# DataTranslator.net
KiCad netlist of a schematic drawn in Altium Designer
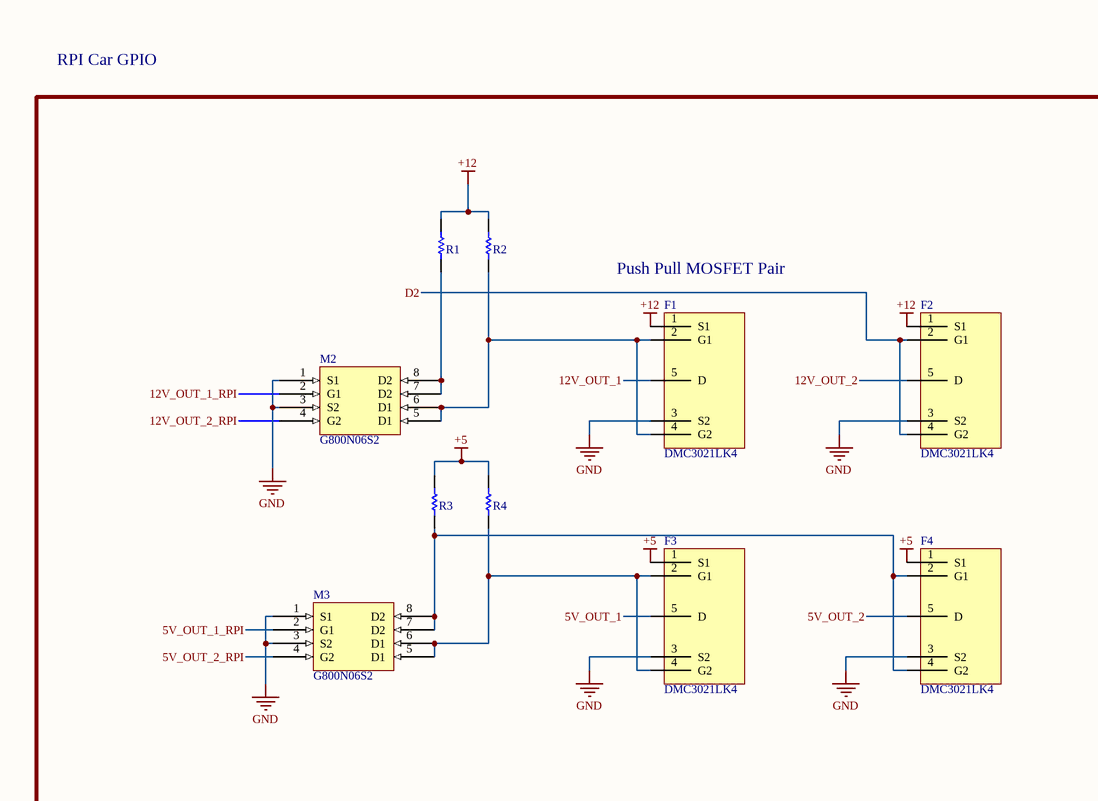
[diagram p0: DataTranslator.SchDoc, left]
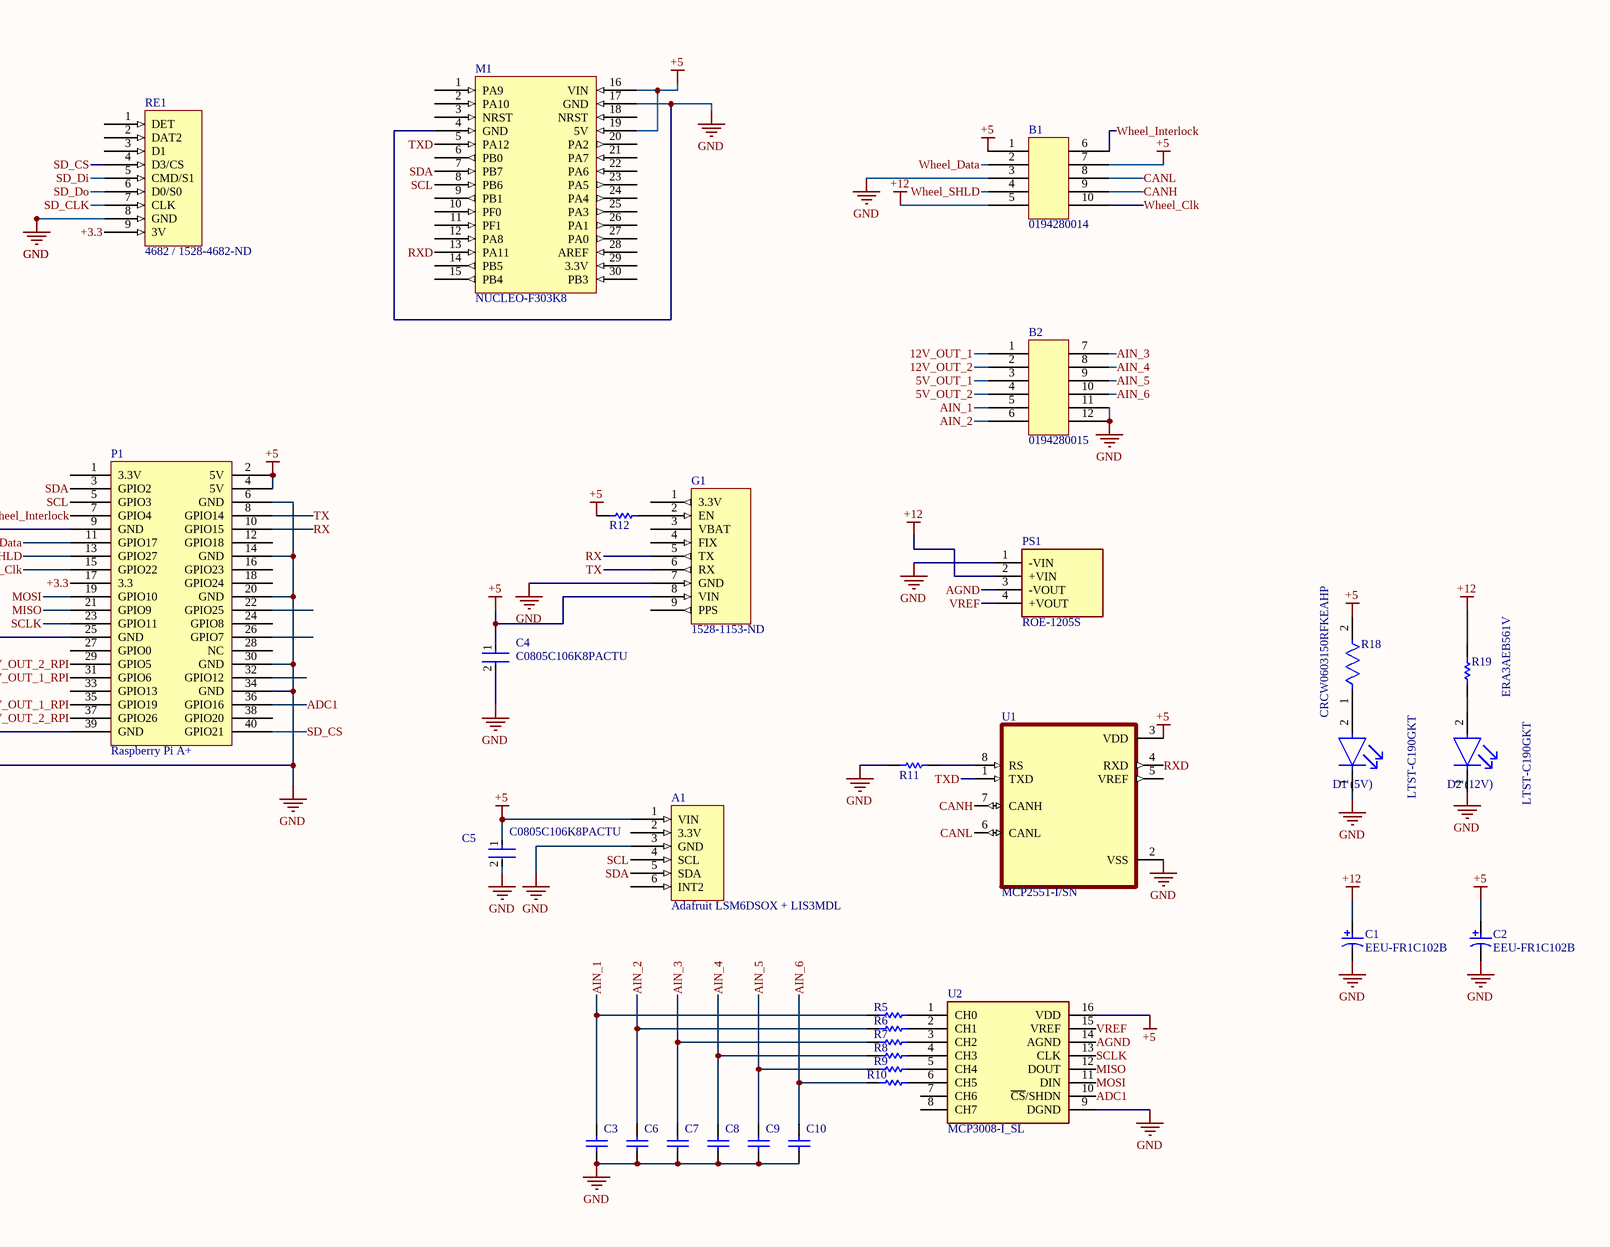
[diagram p1: DataTranslator.SchDoc, right]

(export (version "E")
  (design (tool "Eeschema 10.0.6"))
  (components
    (comp (ref "A1")
      (value "Adafruit LSM6DSOX + LIS3MDL")
      (footprint "4097 Accelerometer")
      (description "ADXL343 - TRIPLE-AXIS ACCELEROMETER")
      (fields
        (field (name "MANUFACTURER") "Adafruit Industries")
        (field (name "MANUFACTURER PART NUMBER") "4097")
      )
      (libsource (lib "DataTranslator") (part "4097"))
    )
    (comp (ref "B1")
      (value "0194280014")
      (footprint "0194280014")
      (description "Combination Line Connector, 10 Contact(s), Male, Solder Terminal")
      (fields (field (name "MANUFACTURER") "Molex"))
      (libsource (lib "DataTranslator") (part "0194280014"))
    )
    (comp (ref "B2")
      (value "0194280015")
      (footprint "0194280015")
      (description "Combination Line Connector")
      (fields (field (name "MANUFACTURER") "Molex") (field (name "MANUFACTURER PART NUMBER") "0194280014"))
      (libsource (lib "DataTranslator") (part "0194280015"))
    )
    (comp (ref "C1")
      (value "EEU-FR1C102B")
      (footprint "PNSC-EEUFM1H221-2")
      (fields (field (name "MANUFACTURER") "Panasonic"))
      (libsource (lib "Altium Content Vault") (part "CAP-P-2"))
    )
    (comp (ref "C2")
      (value "EEU-FR1C102B")
      (footprint "PNSC-EEUFM1H221-2")
      (fields (field (name "MANUFACTURER") "Panasonic"))
      (libsource (lib "Altium Content Vault") (part "CAP-P-2"))
    )
    (comp (ref "C3")
      (value "C0805C105K4PACTU")
      (footprint "CAPC2013X145X50LL20T25")
      (fields (field (name "MANUFACTURER") "Kemet"))
      (libsource (lib "Altium Content Vault") (part "CAP"))
    )
    (comp (ref "C4")
      (value "C0805C106K8PACTU")
      (footprint "FP-C0805C-DG-MFG")
      (description "CAP CER 10UF 10V X5R 0805")
      (fields (field (name "TOLERANCE") "10%") (field (name "MANUFACTURER") "Kemet"))
      (libsource (lib "Altium Content Vault") (part "11868f565c42a9108669ba33697ecf6"))
    )
    (comp (ref "C5")
      (value "C0805C106K8PACTU")
      (footprint "FP-C0805C-DG-MFG")
      (description "CAP CER 10UF 10V X5R 0805")
      (fields (field (name "TOLERANCE") "10%") (field (name "MANUFACTURER") "Kemet"))
      (libsource (lib "Altium Content Vault") (part "11868f565c42a9108669ba33697ecf6"))
    )
    (comp (ref "C6")
      (value "C0805C105K4PACTU")
      (footprint "CAPC2013X145X50LL20T25")
      (fields (field (name "MANUFACTURER") "Kemet"))
      (libsource (lib "Altium Content Vault") (part "CAP"))
    )
    (comp (ref "C7")
      (value "C0805C105K4PACTU")
      (footprint "CAPC2013X145X50LL20T25")
      (fields (field (name "MANUFACTURER") "Kemet"))
      (libsource (lib "Altium Content Vault") (part "CAP"))
    )
    (comp (ref "C8")
      (value "C0805C105K4PACTU")
      (footprint "CAPC2013X145X50LL20T25")
      (fields (field (name "MANUFACTURER") "Kemet"))
      (libsource (lib "Altium Content Vault") (part "CAP"))
    )
    (comp (ref "C9")
      (value "C0805C105K4PACTU")
      (footprint "CAPC2013X145X50LL20T25")
      (fields (field (name "MANUFACTURER") "Kemet"))
      (libsource (lib "Altium Content Vault") (part "CAP"))
    )
    (comp (ref "C10")
      (value "C0805C105K4PACTU")
      (footprint "CAPC2013X145X50LL20T25")
      (fields (field (name "MANUFACTURER") "Kemet"))
      (libsource (lib "Altium Content Vault") (part "CAP"))
    )
    (comp (ref "D1 (5V)")
      (value "LTST-C190GKT")
      (footprint "FP-LTST-C190GKT-MFG")
      (description "LED GREEN CLEAR CHIP SMD")
      (fields (field (name "VOLTAGE") "2V"))
      (libsource (lib "Altium Content Vault") (part "8706943c75ba83719d021d2fdc84c58"))
    )
    (comp (ref "D2 (12V)")
      (value "LTST-C190GKT")
      (footprint "FP-LTST-C190GKT-MFG")
      (description "LED GREEN CLEAR CHIP SMD")
      (fields (field (name "VOLTAGE") "2V"))
      (libsource (lib "Altium Content Vault") (part "8706943c75ba83719d021d2fdc84c58"))
    )
    (comp (ref "F1")
      (value "DMC3021LK4")
      (footprint "DMC3021LK4")
      (fields
        (field (name "MANUFACTURER") "Diodes")
        (field (name "MANUFACTURER PART NUMBER") "DMC3021LK4-13")
      )
      (libsource (lib "DataTranslator") (part "DMC3021LK4"))
    )
    (comp (ref "F2")
      (value "DMC3021LK4")
      (footprint "DMC3021LK4")
      (fields
        (field (name "MANUFACTURER") "Diodes")
        (field (name "MANUFACTURER PART NUMBER") "DMC3021LK4-13")
      )
      (libsource (lib "DataTranslator") (part "DMC3021LK4"))
    )
    (comp (ref "F3")
      (value "DMC3021LK4")
      (footprint "DMC3021LK4")
      (fields
        (field (name "MANUFACTURER") "Diodes")
        (field (name "MANUFACTURER PART NUMBER") "DMC3021LK4-13")
      )
      (libsource (lib "DataTranslator") (part "DMC3021LK4"))
    )
    (comp (ref "F4")
      (value "DMC3021LK4")
      (footprint "DMC3021LK4")
      (fields
        (field (name "MANUFACTURER") "Diodes")
        (field (name "MANUFACTURER PART NUMBER") "DMC3021LK4-13")
      )
      (libsource (lib "DataTranslator") (part "DMC3021LK4"))
    )
    (comp (ref "G1")
      (value "1528-1153-ND")
      (footprint "GPS")
      (description "GPS BREAKOUT 66CH W/10HZ UPDATES")
      (fields
        (field (name "MANUFACTURER") "Adafruit Industries")
        (field (name "MANUFACTURER PART NUMBER") "746")
      )
      (libsource (lib "DataTranslator") (part "1528-1153-ND"))
    )
    (comp (ref "M1")
      (value "NUCLEO-F303K8")
      (footprint "STM Footprint")
      (description "Boards/Accessories")
      (fields (field (name "MANUFACTURER") "STMicroelectronics"))
      (libsource (lib "DataTranslator") (part "NUCLEO-F303K8"))
    )
    (comp (ref "M2")
      (value "G800N06S2")
      (footprint "G800N06S2")
      (description "DUAL N-Channel Enhancement Mode Power MOSFET")
      (fields (field (name "MANUFACTURER") "GoFord"))
      (libsource (lib "DataTranslator") (part "G800N06S2"))
    )
    (comp (ref "M3")
      (value "G800N06S2")
      (footprint "G800N06S2")
      (description "DUAL N-Channel Enhancement Mode Power MOSFET")
      (fields (field (name "MANUFACTURER") "GoFord"))
      (libsource (lib "DataTranslator") (part "G800N06S2"))
    )
    (comp (ref "P1")
      (value "Raspberry Pi A+")
      (footprint "Raspberry Pi A+")
      (description "SINGLE BOARD COMPUTER 700MHZ 256")
      (fields
        (field (name "MANUFACTURER") "Raspberry Pi")
        (field (name "MANUFACTURER PART NUMBER") "RASPBERRY PI A+")
      )
      (libsource (lib "DataTranslator") (part "Raspberry Pi A+"))
    )
    (comp (ref "PS1")
      (value "ROE-1205S")
      (footprint "ROE-1205S")
      (description "Recom Through Hole 1W Isolated DC-DC Converter, I/O isolation 1kV dc, Vout 5V dc")
      (fields (field (name "MOUSER PART NUMBER") "919-ROE-1205S"))
      (libsource (lib "DataTranslator") (part "ROE-1205S"))
    )
    (comp (ref "R1")
      (value "RC0805FR-0710KL")
      (footprint "RESC2013X60X35NL10T20")
      (description "Chip Resistor, 10 KOhm, +/- 1%, 0.125 W, -55 to 155 degC, 0805 (2012 Metric), RoHS, Tape and Reel")
      (fields (field (name "MANUFACTURER") "Yageo"))
      (libsource (lib "Altium Content Vault") (part "RES-2"))
    )
    (comp (ref "R2")
      (value "RC0805FR-0710KL")
      (footprint "RESC2013X60X35NL10T20")
      (description "Chip Resistor, 10 KOhm, +/- 1%, 0.125 W, -55 to 155 degC, 0805 (2012 Metric), RoHS, Tape and Reel")
      (fields (field (name "MANUFACTURER") "Yageo"))
      (libsource (lib "Altium Content Vault") (part "RES-2"))
    )
    (comp (ref "R3")
      (value "RC0805FR-0710KL")
      (footprint "RESC2013X60X35NL10T20")
      (description "Chip Resistor, 10 KOhm, +/- 1%, 0.125 W, -55 to 155 degC, 0805 (2012 Metric), RoHS, Tape and Reel")
      (fields (field (name "MANUFACTURER") "Yageo"))
      (libsource (lib "Altium Content Vault") (part "RES-2"))
    )
    (comp (ref "R4")
      (value "RC0805FR-0710KL")
      (footprint "RESC2013X60X35NL10T20")
      (description "Chip Resistor, 10 KOhm, +/- 1%, 0.125 W, -55 to 155 degC, 0805 (2012 Metric), RoHS, Tape and Reel")
      (fields (field (name "MANUFACTURER") "Yageo"))
      (libsource (lib "Altium Content Vault") (part "RES-2"))
    )
    (comp (ref "R5")
      (value "RC0805FR-0710KL")
      (footprint "RESC2013X60X35NL10T20")
      (description "Chip Resistor, 10 KOhm, +/- 1%, 0.125 W, -55 to 155 degC, 0805 (2012 Metric), RoHS, Tape and Reel")
      (fields (field (name "MANUFACTURER") "Yageo"))
      (libsource (lib "Altium Content Vault") (part "RES-2"))
    )
    (comp (ref "R6")
      (value "RC0805FR-0710KL")
      (footprint "RESC2013X60X35NL10T20")
      (description "Chip Resistor, 10 KOhm, +/- 1%, 0.125 W, -55 to 155 degC, 0805 (2012 Metric), RoHS, Tape and Reel")
      (fields (field (name "MANUFACTURER") "Yageo"))
      (libsource (lib "Altium Content Vault") (part "RES-2"))
    )
    (comp (ref "R7")
      (value "RC0805FR-0710KL")
      (footprint "RESC2013X60X35NL10T20")
      (description "Chip Resistor, 10 KOhm, +/- 1%, 0.125 W, -55 to 155 degC, 0805 (2012 Metric), RoHS, Tape and Reel")
      (fields (field (name "MANUFACTURER") "Yageo"))
      (libsource (lib "Altium Content Vault") (part "RES-2"))
    )
    (comp (ref "R8")
      (value "RC0805FR-0710KL")
      (footprint "RESC2013X60X35NL10T20")
      (description "Chip Resistor, 10 KOhm, +/- 1%, 0.125 W, -55 to 155 degC, 0805 (2012 Metric), RoHS, Tape and Reel")
      (fields (field (name "MANUFACTURER") "Yageo"))
      (libsource (lib "Altium Content Vault") (part "RES-2"))
    )
    (comp (ref "R9")
      (value "RC0805FR-0710KL")
      (footprint "RESC2013X60X35NL10T20")
      (description "Chip Resistor, 10 KOhm, +/- 1%, 0.125 W, -55 to 155 degC, 0805 (2012 Metric), RoHS, Tape and Reel")
      (fields (field (name "MANUFACTURER") "Yageo"))
      (libsource (lib "Altium Content Vault") (part "RES-2"))
    )
    (comp (ref "R10")
      (value "RC0805FR-0710KL")
      (footprint "RESC2013X60X35NL10T20")
      (description "Chip Resistor, 10 KOhm, +/- 1%, 0.125 W, -55 to 155 degC, 0805 (2012 Metric), RoHS, Tape and Reel")
      (fields (field (name "MANUFACTURER") "Yageo"))
      (libsource (lib "Altium Content Vault") (part "RES-2"))
    )
    (comp (ref "R11")
      (value "RC0805FR-0710KL")
      (footprint "RESC2013X60X35NL10T20")
      (description "Chip Resistor, 10 KOhm, +/- 1%, 0.125 W, -55 to 155 degC, 0805 (2012 Metric), RoHS, Tape and Reel")
      (fields (field (name "MANUFACTURER") "Yageo"))
      (libsource (lib "Altium Content Vault") (part "RES-2"))
    )
    (comp (ref "R12")
      (value "RC0805FR-0710KL")
      (footprint "RESC2013X60X35NL10T20")
      (description "Chip Resistor, 10 KOhm, +/- 1%, 0.125 W, -55 to 155 degC, 0805 (2012 Metric), RoHS, Tape and Reel")
      (fields (field (name "MANUFACTURER") "Yageo"))
      (libsource (lib "Altium Content Vault") (part "RES-2"))
    )
    (comp (ref "R18")
      (value "CRCW0603150RFKEAHP")
      (footprint "FP-CRCW0603-HPe3-MFG")
      (description "RES Thick Film, 150Ω, 1%, 0.33W, 100ppm/°C, 0603")
      (fields (field (name "TOLERANCE") "1%"))
      (libsource (lib "Altium Content Vault") (part "1029c3af85768c4190bb7ad29bc67b5"))
    )
    (comp (ref "R19")
      (value "ERA3AEB561V")
      (footprint "RESC1608X55X30LL20T20")
      (fields (field (name "MANUFACTURER") "Panasonic"))
      (libsource (lib "Altium Content Vault") (part "RES"))
    )
    (comp (ref "RE1")
      (value "4682 / 1528-4682-ND")
      (footprint "SDCARD")
      (description "MICROSD SPI/SPIO BREAKOUT BOARD")
      (fields
        (field (name "MANUFACTURER") "Adafruit Industries")
        (field (name "MANUFACTURER PART NUMBER") "4682")
      )
      (libsource (lib "DataTranslator") (part "4682"))
    )
    (comp (ref "U1")
      (value "MCP2551-I/SN")
      (footprint "CAN Transceiver")
      (description "CAN Transceiver, 1-Trnsvr, PDSO8")
      (fields (field (name "MANUFACTURER") "Microchip"))
      (libsource (lib "DataTranslator") (part "MCP2551-I/SN"))
    )
    (comp (ref "U2")
      (value "MCP3008-I_SL")
      (footprint "SOIC127P600X175-16N")
      (fields
        (field (name "MANUFACTURER_PART_NUMBER") "MCP3008-I/SL")
        (field (name "MOUSER PART NUMBER") "579-MCP3008-I/SL")
      )
      (libsource (lib "DataTranslator") (part "MCP3008-I_SL"))
    )
  )
  (nets
    (net (code "1") (name "+5") (class "Default")
      (node (ref "A1") (pin "1") (pinfunction "VIN_1") (pintype "input"))
      (node (ref "B1") (pin "1") (pintype "passive"))
      (node (ref "B1") (pin "7") (pintype "passive"))
      (node (ref "C2") (pin "1") (pinfunction "1_1") (pintype "passive"))
      (node (ref "C4") (pin "1") (pinfunction "1_1") (pintype "passive"))
      (node (ref "C5") (pin "1") (pinfunction "1_1") (pintype "passive"))
      (node (ref "F3") (pin "1") (pinfunction "S1_1") (pintype "passive"))
      (node (ref "F4") (pin "1") (pinfunction "S1_1") (pintype "passive"))
      (node (ref "G1") (pin "8") (pinfunction "VIN_8") (pintype "input"))
      (node (ref "M1") (pin "16") (pinfunction "VIN_16") (pintype "input"))
      (node (ref "M1") (pin "19") (pinfunction "5V_19") (pintype "input"))
      (node (ref "P1") (pin "2") (pinfunction "5V_2") (pintype "passive"))
      (node (ref "P1") (pin "4") (pinfunction "5V_4") (pintype "passive"))
      (node (ref "R12") (pin "1") (pinfunction "1_1") (pintype "passive"))
      (node (ref "R18") (pin "2") (pinfunction "2_2") (pintype "passive"))
      (node (ref "R3") (pin "2") (pinfunction "2_2") (pintype "passive"))
      (node (ref "R4") (pin "2") (pinfunction "2_2") (pintype "passive"))
      (node (ref "U1") (pin "3") (pinfunction "VDD_3") (pintype "power_in"))
      (node (ref "U2") (pin "16") (pinfunction "VDD_16") (pintype "passive"))
    )
    (net (code "2") (name "+12") (class "Default")
      (node (ref "B1") (pin "5") (pintype "passive"))
      (node (ref "C1") (pin "1") (pinfunction "1_1") (pintype "passive"))
      (node (ref "F1") (pin "1") (pinfunction "S1_1") (pintype "passive"))
      (node (ref "F2") (pin "1") (pinfunction "S1_1") (pintype "passive"))
      (node (ref "PS1") (pin "2") (pinfunction "+VIN_2") (pintype "passive"))
      (node (ref "R1") (pin "2") (pinfunction "2_2") (pintype "passive"))
      (node (ref "R19") (pin "2") (pinfunction "2_2") (pintype "passive"))
      (node (ref "R2") (pin "2") (pinfunction "2_2") (pintype "passive"))
    )
    (net (code "3") (name "/+3.3") (class "Default")
      (node (ref "P1") (pin "17") (pinfunction "3.3_17") (pintype "passive"))
      (node (ref "RE1") (pin "9") (pinfunction "3V_9") (pintype "input"))
    )
    (net (code "4") (name "/5V_OUT_1") (class "Default")
      (node (ref "B2") (pin "3") (pintype "passive"))
      (node (ref "F3") (pin "5") (pinfunction "D_5") (pintype "passive"))
    )
    (net (code "5") (name "/5V_OUT_1_RPI") (class "Default")
      (node (ref "M3") (pin "2") (pinfunction "G1_2") (pintype "input"))
      (node (ref "P1") (pin "35") (pinfunction "GPIO19_35") (pintype "passive"))
    )
    (net (code "6") (name "/5V_OUT_2") (class "Default")
      (node (ref "B2") (pin "4") (pintype "passive"))
      (node (ref "F4") (pin "5") (pinfunction "D_5") (pintype "passive"))
    )
    (net (code "7") (name "/5V_OUT_2_RPI") (class "Default")
      (node (ref "M3") (pin "4") (pinfunction "G2_4") (pintype "input"))
      (node (ref "P1") (pin "37") (pinfunction "GPIO26_37") (pintype "passive"))
    )
    (net (code "8") (name "/12V_OUT_1") (class "Default")
      (node (ref "B2") (pin "1") (pintype "passive"))
      (node (ref "F1") (pin "5") (pinfunction "D_5") (pintype "passive"))
    )
    (net (code "9") (name "/12V_OUT_1_RPI") (class "Default")
      (node (ref "M2") (pin "2") (pinfunction "G1_2") (pintype "input"))
      (node (ref "P1") (pin "31") (pinfunction "GPIO6_31") (pintype "passive"))
    )
    (net (code "10") (name "/12V_OUT_2") (class "Default")
      (node (ref "B2") (pin "2") (pintype "passive"))
      (node (ref "F2") (pin "5") (pinfunction "D_5") (pintype "passive"))
    )
    (net (code "11") (name "/12V_OUT_2_RPI") (class "Default")
      (node (ref "M2") (pin "4") (pinfunction "G2_4") (pintype "input"))
      (node (ref "P1") (pin "29") (pinfunction "GPIO5_29") (pintype "passive"))
    )
    (net (code "12") (name "/ADC1") (class "Default")
      (node (ref "P1") (pin "36") (pinfunction "GPIO16_36") (pintype "passive"))
      (node (ref "U2") (pin "10") (pinfunction "~{CS}/SHDN_10") (pintype "passive"))
    )
    (net (code "13") (name "/AGND") (class "Default")
      (node (ref "PS1") (pin "3") (pinfunction "-VOUT_3") (pintype "passive"))
      (node (ref "U2") (pin "14") (pinfunction "AGND_14") (pintype "passive"))
    )
    (net (code "14") (name "/AIN_1") (class "Default")
      (node (ref "B2") (pin "5") (pintype "passive"))
      (node (ref "C3") (pin "1") (pinfunction "1_1") (pintype "passive"))
      (node (ref "R5") (pin "1") (pinfunction "1_1") (pintype "passive"))
    )
    (net (code "15") (name "/AIN_2") (class "Default")
      (node (ref "B2") (pin "6") (pintype "passive"))
      (node (ref "C6") (pin "1") (pinfunction "1_1") (pintype "passive"))
      (node (ref "R6") (pin "1") (pinfunction "1_1") (pintype "passive"))
    )
    (net (code "16") (name "/AIN_3") (class "Default")
      (node (ref "B2") (pin "7") (pintype "passive"))
      (node (ref "C7") (pin "1") (pinfunction "1_1") (pintype "passive"))
      (node (ref "R7") (pin "1") (pinfunction "1_1") (pintype "passive"))
    )
    (net (code "17") (name "/AIN_4") (class "Default")
      (node (ref "B2") (pin "8") (pintype "passive"))
      (node (ref "C8") (pin "1") (pinfunction "1_1") (pintype "passive"))
      (node (ref "R8") (pin "1") (pinfunction "1_1") (pintype "passive"))
    )
    (net (code "18") (name "/AIN_5") (class "Default")
      (node (ref "B2") (pin "9") (pintype "passive"))
      (node (ref "C9") (pin "1") (pinfunction "1_1") (pintype "passive"))
      (node (ref "R9") (pin "1") (pinfunction "1_1") (pintype "passive"))
    )
    (net (code "19") (name "/AIN_6") (class "Default")
      (node (ref "B2") (pin "10") (pintype "passive"))
      (node (ref "C10") (pin "1") (pinfunction "1_1") (pintype "passive"))
      (node (ref "R10") (pin "1") (pinfunction "1_1") (pintype "passive"))
    )
    (net (code "20") (name "/CANH") (class "Default")
      (node (ref "B1") (pin "9") (pintype "passive"))
      (node (ref "U1") (pin "7") (pinfunction "CANH_7") (pintype "bidirectional"))
    )
    (net (code "21") (name "/CANL") (class "Default")
      (node (ref "B1") (pin "8") (pintype "passive"))
      (node (ref "U1") (pin "6") (pinfunction "CANL_6") (pintype "bidirectional"))
    )
    (net (code "22") (name "/D2") (class "Default")
      (node (ref "F2") (pin "2") (pinfunction "G1_2") (pintype "passive"))
      (node (ref "F2") (pin "4") (pinfunction "G2_4") (pintype "passive"))
    )
    (net (code "23") (name "/MISO") (class "Default")
      (node (ref "P1") (pin "21") (pinfunction "GPIO9_21") (pintype "passive"))
      (node (ref "U2") (pin "12") (pinfunction "DOUT_12") (pintype "passive"))
    )
    (net (code "24") (name "/MOSI") (class "Default")
      (node (ref "P1") (pin "19") (pinfunction "GPIO10_19") (pintype "passive"))
      (node (ref "U2") (pin "11") (pinfunction "DIN_11") (pintype "passive"))
    )
    (net (code "25") (name "/RX") (class "Default")
      (node (ref "G1") (pin "5") (pinfunction "TX_5") (pintype "output"))
      (node (ref "P1") (pin "10") (pinfunction "GPIO15_10") (pintype "passive"))
    )
    (net (code "26") (name "/RXD") (class "Default")
      (node (ref "M1") (pin "13") (pinfunction "PA11_13") (pintype "input"))
      (node (ref "U1") (pin "4") (pinfunction "RXD_4") (pintype "output"))
    )
    (net (code "27") (name "/SCL") (class "Default")
      (node (ref "A1") (pin "4") (pinfunction "SCL_4") (pintype "input"))
      (node (ref "M1") (pin "8") (pinfunction "PB6_8") (pintype "input"))
      (node (ref "P1") (pin "5") (pinfunction "GPIO3_5") (pintype "passive"))
    )
    (net (code "28") (name "/SCLK") (class "Default")
      (node (ref "P1") (pin "23") (pinfunction "GPIO11_23") (pintype "passive"))
      (node (ref "U2") (pin "13") (pinfunction "CLK_13") (pintype "passive"))
    )
    (net (code "29") (name "/SDA") (class "Default")
      (node (ref "A1") (pin "5") (pinfunction "SDA_5") (pintype "input"))
      (node (ref "M1") (pin "7") (pinfunction "PB7_7") (pintype "input"))
      (node (ref "P1") (pin "3") (pinfunction "GPIO2_3") (pintype "passive"))
    )
    (net (code "30") (name "/SD_CLK") (class "Default")
      (node (ref "RE1") (pin "7") (pinfunction "CLK_7") (pintype "input"))
    )
    (net (code "31") (name "/SD_CS") (class "Default")
      (node (ref "P1") (pin "40") (pinfunction "GPIO21_40") (pintype "passive"))
      (node (ref "RE1") (pin "4") (pinfunction "D3/CS_4") (pintype "input"))
    )
    (net (code "32") (name "/SD_Di") (class "Default")
      (node (ref "RE1") (pin "5") (pinfunction "CMD/S1_5") (pintype "input"))
    )
    (net (code "33") (name "/SD_Do") (class "Default")
      (node (ref "RE1") (pin "6") (pinfunction "D0/S0_6") (pintype "input"))
    )
    (net (code "34") (name "/TX") (class "Default")
      (node (ref "G1") (pin "6") (pinfunction "RX_6") (pintype "output"))
      (node (ref "P1") (pin "8") (pinfunction "GPIO14_8") (pintype "passive"))
    )
    (net (code "35") (name "/TXD") (class "Default")
      (node (ref "M1") (pin "5") (pinfunction "PA12_5") (pintype "input"))
      (node (ref "U1") (pin "1") (pinfunction "TXD_1") (pintype "input"))
    )
    (net (code "36") (name "/VREF") (class "Default")
      (node (ref "PS1") (pin "4") (pinfunction "+VOUT_4") (pintype "passive"))
      (node (ref "U2") (pin "15") (pinfunction "VREF_15") (pintype "passive"))
    )
    (net (code "37") (name "/Wheel_Clk") (class "Default")
      (node (ref "B1") (pin "10") (pintype "passive"))
      (node (ref "P1") (pin "15") (pinfunction "GPIO22_15") (pintype "passive"))
    )
    (net (code "38") (name "/Wheel_Data") (class "Default")
      (node (ref "B1") (pin "2") (pintype "passive"))
      (node (ref "P1") (pin "11") (pinfunction "GPIO17_11") (pintype "passive"))
    )
    (net (code "39") (name "/Wheel_Interlock") (class "Default")
      (node (ref "B1") (pin "6") (pintype "passive"))
      (node (ref "P1") (pin "7") (pinfunction "GPIO4_7") (pintype "passive"))
    )
    (net (code "40") (name "/Wheel_SHLD") (class "Default")
      (node (ref "B1") (pin "4") (pintype "passive"))
      (node (ref "P1") (pin "13") (pinfunction "GPIO27_13") (pintype "passive"))
    )
    (net (code "41") (name "GND") (class "Default")
      (node (ref "A1") (pin "3") (pinfunction "GND_3") (pintype "input"))
      (node (ref "B1") (pin "3") (pintype "passive"))
      (node (ref "B2") (pin "11") (pintype "passive"))
      (node (ref "B2") (pin "12") (pintype "passive"))
      (node (ref "C1") (pin "2") (pinfunction "2_2") (pintype "passive"))
      (node (ref "C10") (pin "2") (pinfunction "2_2") (pintype "passive"))
      (node (ref "C2") (pin "2") (pinfunction "2_2") (pintype "passive"))
      (node (ref "C3") (pin "2") (pinfunction "2_2") (pintype "passive"))
      (node (ref "C4") (pin "2") (pinfunction "2_2") (pintype "passive"))
      (node (ref "C5") (pin "2") (pinfunction "2_2") (pintype "passive"))
      (node (ref "C6") (pin "2") (pinfunction "2_2") (pintype "passive"))
      (node (ref "C7") (pin "2") (pinfunction "2_2") (pintype "passive"))
      (node (ref "C8") (pin "2") (pinfunction "2_2") (pintype "passive"))
      (node (ref "C9") (pin "2") (pinfunction "2_2") (pintype "passive"))
      (node (ref "D1 (5V)") (pin "1") (pinfunction "C_1") (pintype "passive"))
      (node (ref "D2 (12V)") (pin "1") (pinfunction "C_1") (pintype "passive"))
      (node (ref "F1") (pin "3") (pinfunction "S2_3") (pintype "passive"))
      (node (ref "F2") (pin "3") (pinfunction "S2_3") (pintype "passive"))
      (node (ref "F3") (pin "3") (pinfunction "S2_3") (pintype "passive"))
      (node (ref "F4") (pin "3") (pinfunction "S2_3") (pintype "passive"))
      (node (ref "G1") (pin "7") (pinfunction "GND_7") (pintype "input"))
      (node (ref "M1") (pin "17") (pinfunction "GND_17") (pintype "input"))
      (node (ref "M1") (pin "4") (pinfunction "GND_4") (pintype "input"))
      (node (ref "M2") (pin "1") (pinfunction "S1_1") (pintype "input"))
      (node (ref "M2") (pin "3") (pinfunction "S2_3") (pintype "input"))
      (node (ref "M3") (pin "1") (pinfunction "S1_1") (pintype "input"))
      (node (ref "M3") (pin "3") (pinfunction "S2_3") (pintype "input"))
      (node (ref "P1") (pin "14") (pinfunction "GND_14") (pintype "passive"))
      (node (ref "P1") (pin "20") (pinfunction "GND_20") (pintype "passive"))
      (node (ref "P1") (pin "25") (pinfunction "GND_25") (pintype "passive"))
      (node (ref "P1") (pin "30") (pinfunction "GND_30") (pintype "passive"))
      (node (ref "P1") (pin "34") (pinfunction "GND_34") (pintype "passive"))
      (node (ref "P1") (pin "39") (pinfunction "GND_39") (pintype "passive"))
      (node (ref "P1") (pin "6") (pinfunction "GND_6") (pintype "passive"))
      (node (ref "P1") (pin "9") (pinfunction "GND_9") (pintype "passive"))
      (node (ref "PS1") (pin "1") (pinfunction "-VIN_1") (pintype "passive"))
      (node (ref "R11") (pin "1") (pinfunction "1_1") (pintype "passive"))
      (node (ref "RE1") (pin "8") (pinfunction "GND_8") (pintype "input"))
      (node (ref "U1") (pin "2") (pinfunction "VSS_2") (pintype "power_in"))
      (node (ref "U2") (pin "9") (pinfunction "DGND_9") (pintype "passive"))
    )
    (net (code "42") (name "Net-(D1 (5V)-A)") (class "Default")
      (node (ref "D1 (5V)") (pin "2") (pinfunction "A_2") (pintype "passive"))
      (node (ref "R18") (pin "1") (pinfunction "1_1") (pintype "passive"))
    )
    (net (code "43") (name "Net-(D2 (12V)-A)") (class "Default")
      (node (ref "D2 (12V)") (pin "2") (pinfunction "A_2") (pintype "passive"))
      (node (ref "R19") (pin "1") (pinfunction "1_1") (pintype "passive"))
    )
    (net (code "44") (name "Net-(F1-G1)") (class "Default")
      (node (ref "F1") (pin "2") (pinfunction "G1_2") (pintype "passive"))
      (node (ref "F1") (pin "4") (pinfunction "G2_4") (pintype "passive"))
      (node (ref "M2") (pin "5") (pinfunction "D1_5") (pintype "input"))
      (node (ref "M2") (pin "6") (pinfunction "D1_6") (pintype "input"))
      (node (ref "R2") (pin "1") (pinfunction "1_1") (pintype "passive"))
    )
    (net (code "45") (name "Net-(F3-G1)") (class "Default")
      (node (ref "F3") (pin "2") (pinfunction "G1_2") (pintype "passive"))
      (node (ref "F3") (pin "4") (pinfunction "G2_4") (pintype "passive"))
      (node (ref "M3") (pin "5") (pinfunction "D1_5") (pintype "input"))
      (node (ref "M3") (pin "6") (pinfunction "D1_6") (pintype "input"))
      (node (ref "R4") (pin "1") (pinfunction "1_1") (pintype "passive"))
    )
    (net (code "46") (name "Net-(F4-G1)") (class "Default")
      (node (ref "F4") (pin "2") (pinfunction "G1_2") (pintype "passive"))
      (node (ref "F4") (pin "4") (pinfunction "G2_4") (pintype "passive"))
      (node (ref "M3") (pin "7") (pinfunction "D2_7") (pintype "input"))
      (node (ref "M3") (pin "8") (pinfunction "D2_8") (pintype "input"))
      (node (ref "R3") (pin "1") (pinfunction "1_1") (pintype "passive"))
    )
    (net (code "47") (name "Net-(G1-EN)") (class "Default")
      (node (ref "G1") (pin "2") (pinfunction "EN_2") (pintype "input"))
      (node (ref "R12") (pin "2") (pinfunction "2_2") (pintype "passive"))
    )
    (net (code "48") (name "Net-(M2-D2-Pad7)") (class "Default")
      (node (ref "M2") (pin "7") (pinfunction "D2_7") (pintype "input"))
      (node (ref "M2") (pin "8") (pinfunction "D2_8") (pintype "input"))
      (node (ref "R1") (pin "1") (pinfunction "1_1") (pintype "passive"))
    )
    (net (code "49") (name "Net-(U1-RS)") (class "Default")
      (node (ref "R11") (pin "2") (pinfunction "2_2") (pintype "passive"))
      (node (ref "U1") (pin "8") (pinfunction "RS_8") (pintype "input"))
    )
    (net (code "50") (name "Net-(U2-CH0)") (class "Default")
      (node (ref "R5") (pin "2") (pinfunction "2_2") (pintype "passive"))
      (node (ref "U2") (pin "1") (pinfunction "CH0_1") (pintype "passive"))
    )
    (net (code "51") (name "Net-(U2-CH1)") (class "Default")
      (node (ref "R6") (pin "2") (pinfunction "2_2") (pintype "passive"))
      (node (ref "U2") (pin "2") (pinfunction "CH1_2") (pintype "passive"))
    )
    (net (code "52") (name "Net-(U2-CH2)") (class "Default")
      (node (ref "R7") (pin "2") (pinfunction "2_2") (pintype "passive"))
      (node (ref "U2") (pin "3") (pinfunction "CH2_3") (pintype "passive"))
    )
    (net (code "53") (name "Net-(U2-CH3)") (class "Default")
      (node (ref "R8") (pin "2") (pinfunction "2_2") (pintype "passive"))
      (node (ref "U2") (pin "4") (pinfunction "CH3_4") (pintype "passive"))
    )
    (net (code "54") (name "Net-(U2-CH4)") (class "Default")
      (node (ref "R9") (pin "2") (pinfunction "2_2") (pintype "passive"))
      (node (ref "U2") (pin "5") (pinfunction "CH4_5") (pintype "passive"))
    )
    (net (code "55") (name "Net-(U2-CH5)") (class "Default")
      (node (ref "R10") (pin "2") (pinfunction "2_2") (pintype "passive"))
      (node (ref "U2") (pin "6") (pinfunction "CH5_6") (pintype "passive"))
    )
    (net (code "56") (name "unconnected-(A1-3.3V-Pad2)") (class "Default")
      (node (ref "A1") (pin "2") (pinfunction "3.3V_2") (pintype "input"))
    )
    (net (code "57") (name "unconnected-(A1-INT2-Pad6)") (class "Default")
      (node (ref "A1") (pin "6") (pinfunction "INT2_6") (pintype "input"))
    )
    (net (code "58") (name "unconnected-(G1-3.3V-Pad1)") (class "Default")
      (node (ref "G1") (pin "1") (pinfunction "3.3V_1") (pintype "output"))
    )
    (net (code "59") (name "unconnected-(G1-FIX-Pad4)") (class "Default")
      (node (ref "G1") (pin "4") (pinfunction "FIX_4") (pintype "input"))
    )
    (net (code "60") (name "unconnected-(G1-PPS-Pad9)") (class "Default")
      (node (ref "G1") (pin "9") (pinfunction "PPS_9") (pintype "output"))
    )
    (net (code "61") (name "unconnected-(G1-VBAT-Pad3)") (class "Default")
      (node (ref "G1") (pin "3") (pinfunction "VBAT_3") (pintype "passive"))
    )
    (net (code "62") (name "unconnected-(M1-3.3V-Pad29)") (class "Default")
      (node (ref "M1") (pin "29") (pinfunction "3.3V_29") (pintype "input"))
    )
    (net (code "63") (name "unconnected-(M1-AREF-Pad28)") (class "Default")
      (node (ref "M1") (pin "28") (pinfunction "AREF_28") (pintype "input"))
    )
    (net (code "64") (name "unconnected-(M1-NRST-Pad3)") (class "Default")
      (node (ref "M1") (pin "3") (pinfunction "NRST_3") (pintype "input"))
    )
    (net (code "65") (name "unconnected-(M1-NRST-Pad18)") (class "Default")
      (node (ref "M1") (pin "18") (pinfunction "NRST_18") (pintype "input"))
    )
    (net (code "66") (name "unconnected-(M1-PA0-Pad27)") (class "Default")
      (node (ref "M1") (pin "27") (pinfunction "PA0_27") (pintype "output"))
    )
    (net (code "67") (name "unconnected-(M1-PA1-Pad26)") (class "Default")
      (node (ref "M1") (pin "26") (pinfunction "PA1_26") (pintype "output"))
    )
    (net (code "68") (name "unconnected-(M1-PA2-Pad20)") (class "Default")
      (node (ref "M1") (pin "20") (pinfunction "PA2_20") (pintype "output"))
    )
    (net (code "69") (name "unconnected-(M1-PA3-Pad25)") (class "Default")
      (node (ref "M1") (pin "25") (pinfunction "PA3_25") (pintype "output"))
    )
    (net (code "70") (name "unconnected-(M1-PA4-Pad24)") (class "Default")
      (node (ref "M1") (pin "24") (pinfunction "PA4_24") (pintype "output"))
    )
    (net (code "71") (name "unconnected-(M1-PA5-Pad23)") (class "Default")
      (node (ref "M1") (pin "23") (pinfunction "PA5_23") (pintype "output"))
    )
    (net (code "72") (name "unconnected-(M1-PA6-Pad22)") (class "Default")
      (node (ref "M1") (pin "22") (pinfunction "PA6_22") (pintype "input"))
    )
    (net (code "73") (name "unconnected-(M1-PA7-Pad21)") (class "Default")
      (node (ref "M1") (pin "21") (pinfunction "PA7_21") (pintype "input"))
    )
    (net (code "74") (name "unconnected-(M1-PA8-Pad12)") (class "Default")
      (node (ref "M1") (pin "12") (pinfunction "PA8_12") (pintype "input"))
    )
    (net (code "75") (name "unconnected-(M1-PA9-Pad1)") (class "Default")
      (node (ref "M1") (pin "1") (pinfunction "PA9_1") (pintype "input"))
    )
    (net (code "76") (name "unconnected-(M1-PA10-Pad2)") (class "Default")
      (node (ref "M1") (pin "2") (pinfunction "PA10_2") (pintype "input"))
    )
    (net (code "77") (name "unconnected-(M1-PB0-Pad6)") (class "Default")
      (node (ref "M1") (pin "6") (pinfunction "PB0_6") (pintype "output"))
    )
    (net (code "78") (name "unconnected-(M1-PB1-Pad9)") (class "Default")
      (node (ref "M1") (pin "9") (pinfunction "PB1_9") (pintype "output"))
    )
    (net (code "79") (name "unconnected-(M1-PB3-Pad30)") (class "Default")
      (node (ref "M1") (pin "30") (pinfunction "PB3_30") (pintype "input"))
    )
    (net (code "80") (name "unconnected-(M1-PB4-Pad15)") (class "Default")
      (node (ref "M1") (pin "15") (pinfunction "PB4_15") (pintype "output"))
    )
    (net (code "81") (name "unconnected-(M1-PB5-Pad14)") (class "Default")
      (node (ref "M1") (pin "14") (pinfunction "PB5_14") (pintype "output"))
    )
    (net (code "82") (name "unconnected-(M1-PF0-Pad10)") (class "Default")
      (node (ref "M1") (pin "10") (pinfunction "PF0_10") (pintype "input"))
    )
    (net (code "83") (name "unconnected-(M1-PF1-Pad11)") (class "Default")
      (node (ref "M1") (pin "11") (pinfunction "PF1_11") (pintype "input"))
    )
    (net (code "84") (name "unconnected-(P1-3.3V-Pad1)") (class "Default")
      (node (ref "P1") (pin "1") (pinfunction "3.3V_1") (pintype "passive"))
    )
    (net (code "85") (name "unconnected-(P1-GPIO0-Pad27)") (class "Default")
      (node (ref "P1") (pin "27") (pinfunction "GPIO0_27") (pintype "passive"))
    )
    (net (code "86") (name "unconnected-(P1-GPIO7-Pad26)") (class "Default")
      (node (ref "P1") (pin "26") (pinfunction "GPIO7_26") (pintype "passive"))
    )
    (net (code "87") (name "unconnected-(P1-GPIO8-Pad24)") (class "Default")
      (node (ref "P1") (pin "24") (pinfunction "GPIO8_24") (pintype "passive"))
    )
    (net (code "88") (name "unconnected-(P1-GPIO12-Pad32)") (class "Default")
      (node (ref "P1") (pin "32") (pinfunction "GPIO12_32") (pintype "passive"))
    )
    (net (code "89") (name "unconnected-(P1-GPIO13-Pad33)") (class "Default")
      (node (ref "P1") (pin "33") (pinfunction "GPIO13_33") (pintype "passive"))
    )
    (net (code "90") (name "unconnected-(P1-GPIO18-Pad12)") (class "Default")
      (node (ref "P1") (pin "12") (pinfunction "GPIO18_12") (pintype "passive"))
    )
    (net (code "91") (name "unconnected-(P1-GPIO20-Pad38)") (class "Default")
      (node (ref "P1") (pin "38") (pinfunction "GPIO20_38") (pintype "passive"))
    )
    (net (code "92") (name "unconnected-(P1-GPIO23-Pad16)") (class "Default")
      (node (ref "P1") (pin "16") (pinfunction "GPIO23_16") (pintype "passive"))
    )
    (net (code "93") (name "unconnected-(P1-GPIO24-Pad18)") (class "Default")
      (node (ref "P1") (pin "18") (pinfunction "GPIO24_18") (pintype "passive"))
    )
    (net (code "94") (name "unconnected-(P1-GPIO25-Pad22)") (class "Default")
      (node (ref "P1") (pin "22") (pinfunction "GPIO25_22") (pintype "passive"))
    )
    (net (code "95") (name "unconnected-(P1-NC-Pad28)") (class "Default")
      (node (ref "P1") (pin "28") (pinfunction "NC_28") (pintype "passive"))
    )
    (net (code "96") (name "unconnected-(RE1-D1-Pad3)") (class "Default")
      (node (ref "RE1") (pin "3") (pinfunction "D1_3") (pintype "input"))
    )
    (net (code "97") (name "unconnected-(RE1-DAT2-Pad2)") (class "Default")
      (node (ref "RE1") (pin "2") (pinfunction "DAT2_2") (pintype "input"))
    )
    (net (code "98") (name "unconnected-(RE1-DET-Pad1)") (class "Default")
      (node (ref "RE1") (pin "1") (pinfunction "DET_1") (pintype "input"))
    )
    (net (code "99") (name "unconnected-(U1-VREF-Pad5)") (class "Default")
      (node (ref "U1") (pin "5") (pinfunction "VREF_5") (pintype "output"))
    )
    (net (code "100") (name "unconnected-(U2-CH6-Pad7)") (class "Default")
      (node (ref "U2") (pin "7") (pinfunction "CH6_7") (pintype "passive"))
    )
    (net (code "101") (name "unconnected-(U2-CH7-Pad8)") (class "Default")
      (node (ref "U2") (pin "8") (pinfunction "CH7_8") (pintype "passive"))
    )
  )
)
